# untitled.net
KiCad netlist of a schematic drawn in EAGLE
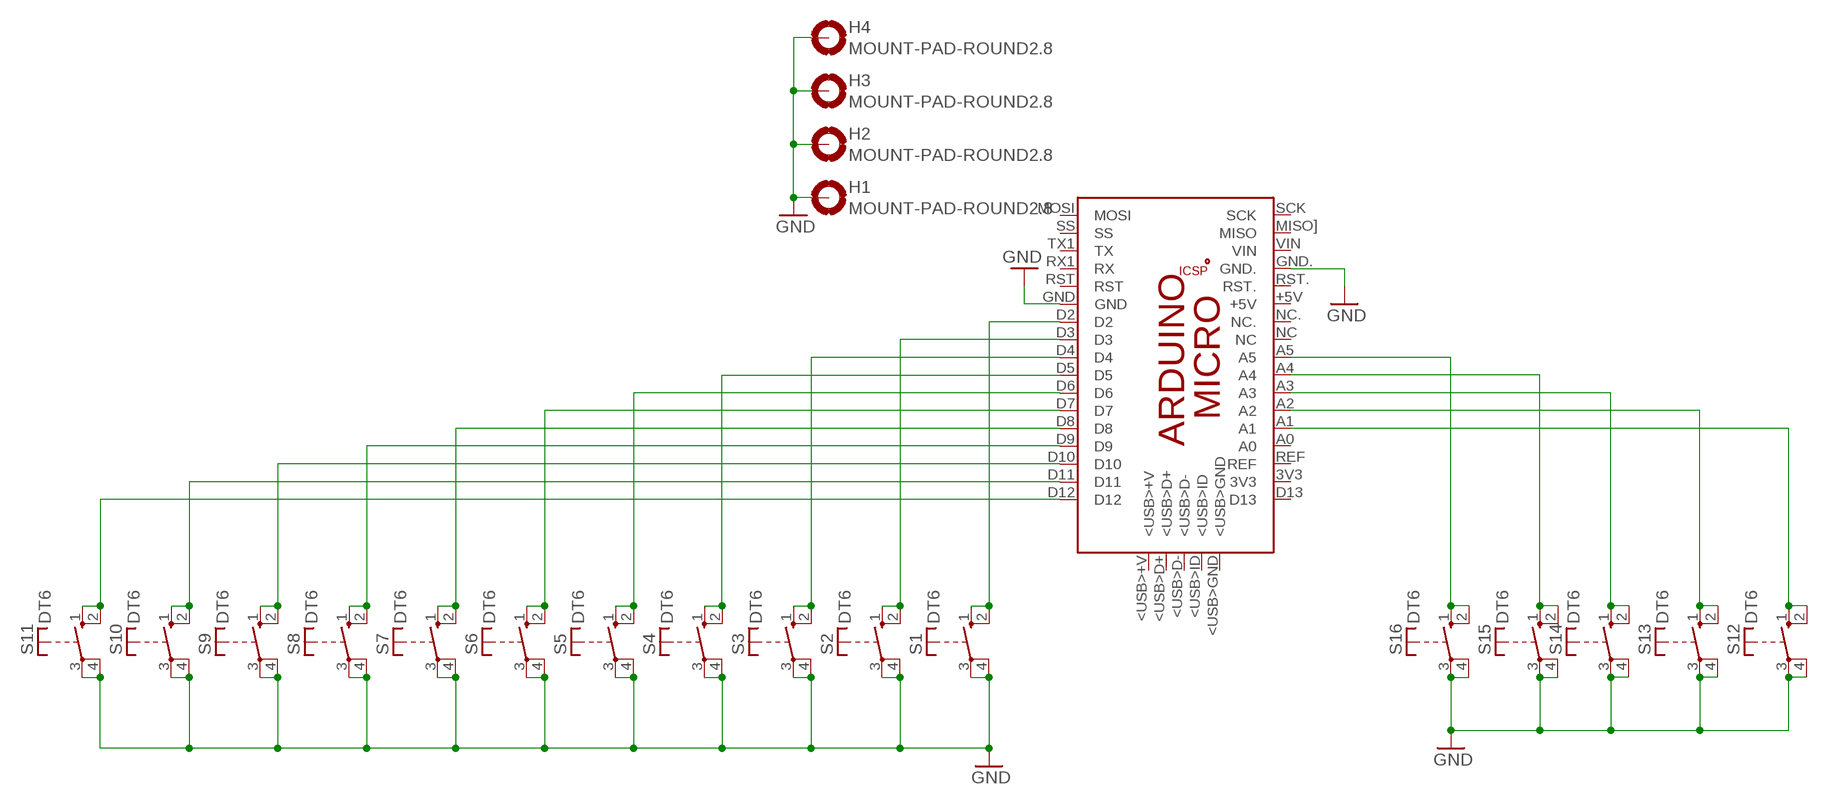
[diagram p0: schematic, sheet 1]

(export (version "E")
  (design (tool "Eeschema 10.0.6"))
  (components
    (comp (ref "H1")
      (value "MOUNT-PAD-ROUND2.8")
      (footprint "eagle-import:2,8-PAD")
      (libsource (lib "eagle-import") (part "MOUNT-PAD-ROUND2.8"))
    )
    (comp (ref "H2")
      (value "MOUNT-PAD-ROUND2.8")
      (footprint "eagle-import:2,8-PAD")
      (libsource (lib "eagle-import") (part "MOUNT-PAD-ROUND2.8"))
    )
    (comp (ref "H3")
      (value "MOUNT-PAD-ROUND2.8")
      (footprint "eagle-import:2,8-PAD")
      (libsource (lib "eagle-import") (part "MOUNT-PAD-ROUND2.8"))
    )
    (comp (ref "H4")
      (value "MOUNT-PAD-ROUND2.8")
      (footprint "eagle-import:2,8-PAD")
      (libsource (lib "eagle-import") (part "MOUNT-PAD-ROUND2.8"))
    )
    (comp (ref "PCB2")
      (value "ARDUINO_MICRO")
      (footprint "eagle-import:ARDUINO_MICRO")
      (libsource (lib "eagle-import") (part "ARDUINO_MICRO"))
    )
    (comp (ref "S1")
      (value "DT6")
      (footprint "eagle-import:DT6")
      (libsource (lib "eagle-import") (part "DT6"))
    )
    (comp (ref "S2")
      (value "DT6")
      (footprint "eagle-import:DT6")
      (libsource (lib "eagle-import") (part "DT6"))
    )
    (comp (ref "S3")
      (value "DT6")
      (footprint "eagle-import:DT6")
      (libsource (lib "eagle-import") (part "DT6"))
    )
    (comp (ref "S4")
      (value "DT6")
      (footprint "eagle-import:DT6")
      (libsource (lib "eagle-import") (part "DT6"))
    )
    (comp (ref "S5")
      (value "DT6")
      (footprint "eagle-import:DT6")
      (libsource (lib "eagle-import") (part "DT6"))
    )
    (comp (ref "S6")
      (value "DT6")
      (footprint "eagle-import:DT6")
      (libsource (lib "eagle-import") (part "DT6"))
    )
    (comp (ref "S7")
      (value "DT6")
      (footprint "eagle-import:DT6")
      (libsource (lib "eagle-import") (part "DT6"))
    )
    (comp (ref "S8")
      (value "DT6")
      (footprint "eagle-import:DT6")
      (libsource (lib "eagle-import") (part "DT6"))
    )
    (comp (ref "S9")
      (value "DT6")
      (footprint "eagle-import:DT6")
      (libsource (lib "eagle-import") (part "DT6"))
    )
    (comp (ref "S10")
      (value "DT6")
      (footprint "eagle-import:DT6")
      (libsource (lib "eagle-import") (part "DT6"))
    )
    (comp (ref "S11")
      (value "DT6")
      (footprint "eagle-import:DT6")
      (libsource (lib "eagle-import") (part "DT6"))
    )
    (comp (ref "S12")
      (value "DT6")
      (footprint "eagle-import:DT6")
      (libsource (lib "eagle-import") (part "DT6"))
    )
    (comp (ref "S13")
      (value "DT6")
      (footprint "eagle-import:DT6")
      (libsource (lib "eagle-import") (part "DT6"))
    )
    (comp (ref "S14")
      (value "DT6")
      (footprint "eagle-import:DT6")
      (libsource (lib "eagle-import") (part "DT6"))
    )
    (comp (ref "S15")
      (value "DT6")
      (footprint "eagle-import:DT6")
      (libsource (lib "eagle-import") (part "DT6"))
    )
    (comp (ref "S16")
      (value "DT6")
      (footprint "eagle-import:DT6")
      (libsource (lib "eagle-import") (part "DT6"))
    )
  )
  (nets
    (net (code "1") (name "GND") (class "Default")
      (node (ref "H1") (pin "B2,8") (pinfunction "MOUNT_B2,8") (pintype "passive"))
      (node (ref "H2") (pin "B2,8") (pinfunction "MOUNT_B2,8") (pintype "passive"))
      (node (ref "H3") (pin "B2,8") (pinfunction "MOUNT_B2,8") (pintype "passive"))
      (node (ref "H4") (pin "B2,8") (pinfunction "MOUNT_B2,8") (pintype "passive"))
      (node (ref "PCB2") (pin "GND") (pinfunction "GND_GND") (pintype "bidirectional"))
      (node (ref "PCB2") (pin "GND.") (pinfunction "GND._GND.") (pintype "bidirectional"))
      (node (ref "S1") (pin "3") (pinfunction "P_3") (pintype "passive"))
      (node (ref "S1") (pin "4") (pinfunction "P_4") (pintype "passive"))
      (node (ref "S10") (pin "3") (pinfunction "P_3") (pintype "passive"))
      (node (ref "S10") (pin "4") (pinfunction "P_4") (pintype "passive"))
      (node (ref "S11") (pin "3") (pinfunction "P_3") (pintype "passive"))
      (node (ref "S11") (pin "4") (pinfunction "P_4") (pintype "passive"))
      (node (ref "S12") (pin "3") (pinfunction "P_3") (pintype "passive"))
      (node (ref "S12") (pin "4") (pinfunction "P_4") (pintype "passive"))
      (node (ref "S13") (pin "3") (pinfunction "P_3") (pintype "passive"))
      (node (ref "S13") (pin "4") (pinfunction "P_4") (pintype "passive"))
      (node (ref "S14") (pin "3") (pinfunction "P_3") (pintype "passive"))
      (node (ref "S14") (pin "4") (pinfunction "P_4") (pintype "passive"))
      (node (ref "S15") (pin "3") (pinfunction "P_3") (pintype "passive"))
      (node (ref "S15") (pin "4") (pinfunction "P_4") (pintype "passive"))
      (node (ref "S16") (pin "3") (pinfunction "P_3") (pintype "passive"))
      (node (ref "S16") (pin "4") (pinfunction "P_4") (pintype "passive"))
      (node (ref "S2") (pin "3") (pinfunction "P_3") (pintype "passive"))
      (node (ref "S2") (pin "4") (pinfunction "P_4") (pintype "passive"))
      (node (ref "S3") (pin "3") (pinfunction "P_3") (pintype "passive"))
      (node (ref "S3") (pin "4") (pinfunction "P_4") (pintype "passive"))
      (node (ref "S4") (pin "3") (pinfunction "P_3") (pintype "passive"))
      (node (ref "S4") (pin "4") (pinfunction "P_4") (pintype "passive"))
      (node (ref "S5") (pin "3") (pinfunction "P_3") (pintype "passive"))
      (node (ref "S5") (pin "4") (pinfunction "P_4") (pintype "passive"))
      (node (ref "S6") (pin "3") (pinfunction "P_3") (pintype "passive"))
      (node (ref "S6") (pin "4") (pinfunction "P_4") (pintype "passive"))
      (node (ref "S7") (pin "3") (pinfunction "P_3") (pintype "passive"))
      (node (ref "S7") (pin "4") (pinfunction "P_4") (pintype "passive"))
      (node (ref "S8") (pin "3") (pinfunction "P_3") (pintype "passive"))
      (node (ref "S8") (pin "4") (pinfunction "P_4") (pintype "passive"))
      (node (ref "S9") (pin "3") (pinfunction "P_3") (pintype "passive"))
      (node (ref "S9") (pin "4") (pinfunction "P_4") (pintype "passive"))
    )
    (net (code "2") (name "Net-(PCB2-PadA1)") (class "Default")
      (node (ref "PCB2") (pin "A1") (pinfunction "A1_A1") (pintype "bidirectional"))
      (node (ref "S12") (pin "1") (pinfunction "S_1") (pintype "passive"))
      (node (ref "S12") (pin "2") (pinfunction "S_2") (pintype "passive"))
    )
    (net (code "3") (name "Net-(PCB2-PadA2)") (class "Default")
      (node (ref "PCB2") (pin "A2") (pinfunction "A2_A2") (pintype "bidirectional"))
      (node (ref "S13") (pin "1") (pinfunction "S_1") (pintype "passive"))
      (node (ref "S13") (pin "2") (pinfunction "S_2") (pintype "passive"))
    )
    (net (code "4") (name "Net-(PCB2-PadA3)") (class "Default")
      (node (ref "PCB2") (pin "A3") (pinfunction "A3_A3") (pintype "bidirectional"))
      (node (ref "S14") (pin "1") (pinfunction "S_1") (pintype "passive"))
      (node (ref "S14") (pin "2") (pinfunction "S_2") (pintype "passive"))
    )
    (net (code "5") (name "Net-(PCB2-PadA4)") (class "Default")
      (node (ref "PCB2") (pin "A4") (pinfunction "A4_A4") (pintype "bidirectional"))
      (node (ref "S15") (pin "1") (pinfunction "S_1") (pintype "passive"))
      (node (ref "S15") (pin "2") (pinfunction "S_2") (pintype "passive"))
    )
    (net (code "6") (name "Net-(PCB2-PadA5)") (class "Default")
      (node (ref "PCB2") (pin "A5") (pinfunction "A5_A5") (pintype "bidirectional"))
      (node (ref "S16") (pin "1") (pinfunction "S_1") (pintype "passive"))
      (node (ref "S16") (pin "2") (pinfunction "S_2") (pintype "passive"))
    )
    (net (code "7") (name "Net-(PCB2-PadD2)") (class "Default")
      (node (ref "PCB2") (pin "D2") (pinfunction "D2_D2") (pintype "bidirectional"))
      (node (ref "S1") (pin "1") (pinfunction "S_1") (pintype "passive"))
      (node (ref "S1") (pin "2") (pinfunction "S_2") (pintype "passive"))
    )
    (net (code "8") (name "Net-(PCB2-PadD3)") (class "Default")
      (node (ref "PCB2") (pin "D3") (pinfunction "D3_D3") (pintype "bidirectional"))
      (node (ref "S2") (pin "1") (pinfunction "S_1") (pintype "passive"))
      (node (ref "S2") (pin "2") (pinfunction "S_2") (pintype "passive"))
    )
    (net (code "9") (name "Net-(PCB2-PadD4)") (class "Default")
      (node (ref "PCB2") (pin "D4") (pinfunction "D4_D4") (pintype "bidirectional"))
      (node (ref "S3") (pin "1") (pinfunction "S_1") (pintype "passive"))
      (node (ref "S3") (pin "2") (pinfunction "S_2") (pintype "passive"))
    )
    (net (code "10") (name "Net-(PCB2-PadD5)") (class "Default")
      (node (ref "PCB2") (pin "D5") (pinfunction "D5_D5") (pintype "bidirectional"))
      (node (ref "S4") (pin "1") (pinfunction "S_1") (pintype "passive"))
      (node (ref "S4") (pin "2") (pinfunction "S_2") (pintype "passive"))
    )
    (net (code "11") (name "Net-(PCB2-PadD6)") (class "Default")
      (node (ref "PCB2") (pin "D6") (pinfunction "D6_D6") (pintype "bidirectional"))
      (node (ref "S5") (pin "1") (pinfunction "S_1") (pintype "passive"))
      (node (ref "S5") (pin "2") (pinfunction "S_2") (pintype "passive"))
    )
    (net (code "12") (name "Net-(PCB2-PadD7)") (class "Default")
      (node (ref "PCB2") (pin "D7") (pinfunction "D7_D7") (pintype "bidirectional"))
      (node (ref "S6") (pin "1") (pinfunction "S_1") (pintype "passive"))
      (node (ref "S6") (pin "2") (pinfunction "S_2") (pintype "passive"))
    )
    (net (code "13") (name "Net-(PCB2-PadD8)") (class "Default")
      (node (ref "PCB2") (pin "D8") (pinfunction "D8_D8") (pintype "bidirectional"))
      (node (ref "S7") (pin "1") (pinfunction "S_1") (pintype "passive"))
      (node (ref "S7") (pin "2") (pinfunction "S_2") (pintype "passive"))
    )
    (net (code "14") (name "Net-(PCB2-PadD9)") (class "Default")
      (node (ref "PCB2") (pin "D9") (pinfunction "D9_D9") (pintype "bidirectional"))
      (node (ref "S8") (pin "1") (pinfunction "S_1") (pintype "passive"))
      (node (ref "S8") (pin "2") (pinfunction "S_2") (pintype "passive"))
    )
    (net (code "15") (name "Net-(PCB2-PadD10)") (class "Default")
      (node (ref "PCB2") (pin "D10") (pinfunction "D10_D10") (pintype "bidirectional"))
      (node (ref "S9") (pin "1") (pinfunction "S_1") (pintype "passive"))
      (node (ref "S9") (pin "2") (pinfunction "S_2") (pintype "passive"))
    )
    (net (code "16") (name "Net-(PCB2-PadD11)") (class "Default")
      (node (ref "PCB2") (pin "D11") (pinfunction "D11_D11") (pintype "bidirectional"))
      (node (ref "S10") (pin "1") (pinfunction "S_1") (pintype "passive"))
      (node (ref "S10") (pin "2") (pinfunction "S_2") (pintype "passive"))
    )
    (net (code "17") (name "Net-(PCB2-PadD12)") (class "Default")
      (node (ref "PCB2") (pin "D12") (pinfunction "D12_D12") (pintype "bidirectional"))
      (node (ref "S11") (pin "1") (pinfunction "S_1") (pintype "passive"))
      (node (ref "S11") (pin "2") (pinfunction "S_2") (pintype "passive"))
    )
    (net (code "18") (name "unconnected-(PCB2-MISO-PadMISO])") (class "Default")
      (node (ref "PCB2") (pin "MISO]") (pinfunction "MISO_MISO]") (pintype "bidirectional"))
    )
    (net (code "19") (name "unconnected-(PCB2-Pad+5V)") (class "Default")
      (node (ref "PCB2") (pin "+5V") (pinfunction "+5V_+5V") (pintype "bidirectional"))
    )
    (net (code "20") (name "unconnected-(PCB2-Pad3V3)") (class "Default")
      (node (ref "PCB2") (pin "3V3") (pinfunction "3V3_3V3") (pintype "bidirectional"))
    )
    (net (code "21") (name "unconnected-(PCB2-Pad5V)") (class "Default")
      (node (ref "PCB2") (pin "5V") (pinfunction "5V_5V") (pintype "bidirectional"))
    )
    (net (code "22") (name "unconnected-(PCB2-Pad<USB>+V)") (class "Default")
      (node (ref "PCB2") (pin "<USB>+V") (pinfunction "<USB>+V_<USB>+V") (pintype "bidirectional"))
    )
    (net (code "23") (name "unconnected-(PCB2-Pad<USB>D+)") (class "Default")
      (node (ref "PCB2") (pin "<USB>D+") (pinfunction "<USB>D+_<USB>D+") (pintype "bidirectional"))
    )
    (net (code "24") (name "unconnected-(PCB2-Pad<USB>D-)") (class "Default")
      (node (ref "PCB2") (pin "<USB>D-") (pinfunction "<USB>D-_<USB>D-") (pintype "bidirectional"))
    )
    (net (code "25") (name "unconnected-(PCB2-Pad<USB>GND)") (class "Default")
      (node (ref "PCB2") (pin "<USB>GND") (pinfunction "<USB>GND_<USB>GND") (pintype "bidirectional"))
    )
    (net (code "26") (name "unconnected-(PCB2-Pad<USB>ID)") (class "Default")
      (node (ref "PCB2") (pin "<USB>ID") (pinfunction "<USB>ID_<USB>ID") (pintype "bidirectional"))
    )
    (net (code "27") (name "unconnected-(PCB2-PadA0)") (class "Default")
      (node (ref "PCB2") (pin "A0") (pinfunction "A0_A0") (pintype "bidirectional"))
    )
    (net (code "28") (name "unconnected-(PCB2-PadD13)") (class "Default")
      (node (ref "PCB2") (pin "D13") (pinfunction "D13_D13") (pintype "bidirectional"))
    )
    (net (code "29") (name "unconnected-(PCB2-PadGND_)") (class "Default")
      (node (ref "PCB2") (pin "GND_") (pinfunction "GND__GND_") (pintype "bidirectional"))
    )
    (net (code "30") (name "unconnected-(PCB2-PadMISO.)") (class "Default")
      (node (ref "PCB2") (pin "MISO.") (pinfunction "MISO._MISO.") (pintype "bidirectional"))
    )
    (net (code "31") (name "unconnected-(PCB2-PadMOSI)") (class "Default")
      (node (ref "PCB2") (pin "MOSI") (pinfunction "MOSI_MOSI") (pintype "bidirectional"))
    )
    (net (code "32") (name "unconnected-(PCB2-PadMOSI.)") (class "Default")
      (node (ref "PCB2") (pin "MOSI.") (pinfunction "MOSI._MOSI.") (pintype "bidirectional"))
    )
    (net (code "33") (name "unconnected-(PCB2-PadNC)") (class "Default")
      (node (ref "PCB2") (pin "NC") (pinfunction "NC_NC") (pintype "bidirectional"))
    )
    (net (code "34") (name "unconnected-(PCB2-PadNC.)") (class "Default")
      (node (ref "PCB2") (pin "NC.") (pinfunction "NC._NC.") (pintype "bidirectional"))
    )
    (net (code "35") (name "unconnected-(PCB2-PadREF)") (class "Default")
      (node (ref "PCB2") (pin "REF") (pinfunction "REF_REF") (pintype "bidirectional"))
    )
    (net (code "36") (name "unconnected-(PCB2-PadRESET..)") (class "Default")
      (node (ref "PCB2") (pin "RESET..") (pinfunction "RESET.._RESET..") (pintype "bidirectional"))
    )
    (net (code "37") (name "unconnected-(PCB2-PadRST)") (class "Default")
      (node (ref "PCB2") (pin "RST") (pinfunction "RST_RST") (pintype "bidirectional"))
    )
    (net (code "38") (name "unconnected-(PCB2-PadRST.)") (class "Default")
      (node (ref "PCB2") (pin "RST.") (pinfunction "RST._RST.") (pintype "bidirectional"))
    )
    (net (code "39") (name "unconnected-(PCB2-PadSCK)") (class "Default")
      (node (ref "PCB2") (pin "SCK") (pinfunction "SCK_SCK") (pintype "bidirectional"))
    )
    (net (code "40") (name "unconnected-(PCB2-PadSCK.)") (class "Default")
      (node (ref "PCB2") (pin "SCK.") (pinfunction "SCK._SCK.") (pintype "bidirectional"))
    )
    (net (code "41") (name "unconnected-(PCB2-PadSS)") (class "Default")
      (node (ref "PCB2") (pin "SS") (pinfunction "SS_SS") (pintype "bidirectional"))
    )
    (net (code "42") (name "unconnected-(PCB2-PadVIN)") (class "Default")
      (node (ref "PCB2") (pin "VIN") (pinfunction "VIN_VIN") (pintype "bidirectional"))
    )
    (net (code "43") (name "unconnected-(PCB2-RX-PadRX1)") (class "Default")
      (node (ref "PCB2") (pin "RX1") (pinfunction "RX_RX1") (pintype "bidirectional"))
    )
    (net (code "44") (name "unconnected-(PCB2-TX-PadTX1)") (class "Default")
      (node (ref "PCB2") (pin "TX1") (pinfunction "TX_TX1") (pintype "bidirectional"))
    )
  )
)
